# Sheet1_lora.net
KiCad netlist of a schematic drawn in Altium Designer
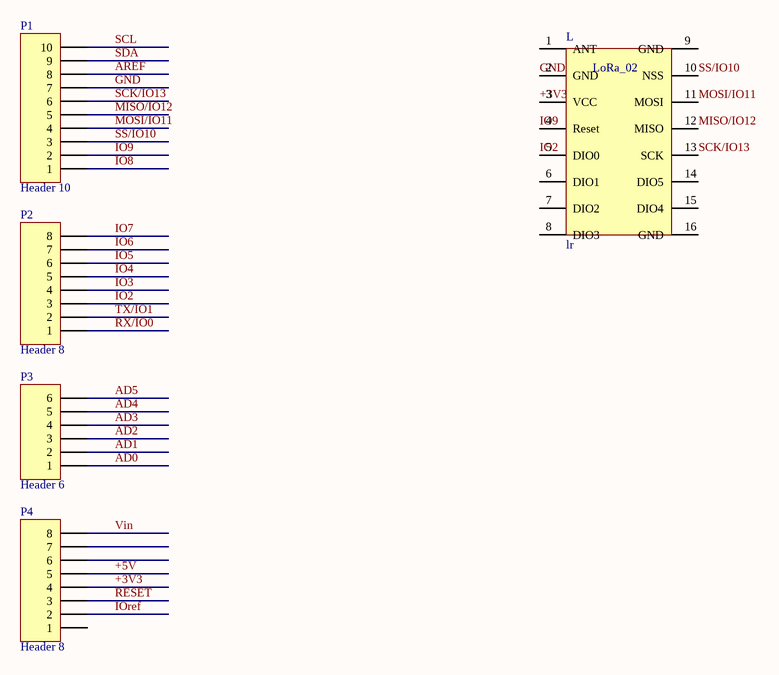
[diagram p0: Sheet1_lora.SchDoc]

(export (version "E")
  (design (tool "Eeschema 10.0.6"))
  (components
    (comp (ref "L") (value "lr") (footprint "LoRa") (libsource (lib "LoRa") (part "LoRa_Ra02")))
    (comp (ref "P1")
      (value "Header 10")
      (footprint "HDR1X10")
      (description "Header, 10-Pin")
      (fields (field (name "PUBLISHER") "Altium Limited"))
      (libsource (lib "Miscellaneous Connectors") (part "Header 10"))
    )
    (comp (ref "P2")
      (value "Header 8")
      (footprint "HDR1X8")
      (description "Header, 8-Pin")
      (fields (field (name "PUBLISHER") "Altium Limited"))
      (libsource (lib "Miscellaneous Connectors") (part "Header 8"))
    )
    (comp (ref "P3")
      (value "Header 6")
      (footprint "HDR1X6")
      (description "Header, 6-Pin")
      (fields (field (name "PUBLISHER") "Altium Limited"))
      (libsource (lib "Miscellaneous Connectors") (part "Header 6"))
    )
    (comp (ref "P4")
      (value "Header 8")
      (footprint "HDR1X8")
      (description "Header, 8-Pin")
      (fields (field (name "PUBLISHER") "Altium Limited"))
      (libsource (lib "Miscellaneous Connectors") (part "Header 8"))
    )
  )
  (nets
    (net (code "1") (name "/+3V3") (class "Default")
      (node (ref "L") (pin "3") (pinfunction "VCC_3") (pintype "passive"))
      (node (ref "P4") (pin "4") (pinfunction "4_4") (pintype "passive"))
    )
    (net (code "2") (name "/+5V") (class "Default")
      (node (ref "P4") (pin "5") (pinfunction "5_5") (pintype "passive"))
    )
    (net (code "3") (name "/AD0") (class "Default")
      (node (ref "P3") (pin "1") (pinfunction "1_1") (pintype "passive"))
    )
    (net (code "4") (name "/AD1") (class "Default")
      (node (ref "P3") (pin "2") (pinfunction "2_2") (pintype "passive"))
    )
    (net (code "5") (name "/AD2") (class "Default")
      (node (ref "P3") (pin "3") (pinfunction "3_3") (pintype "passive"))
    )
    (net (code "6") (name "/AD3") (class "Default")
      (node (ref "P3") (pin "4") (pinfunction "4_4") (pintype "passive"))
    )
    (net (code "7") (name "/AD4") (class "Default")
      (node (ref "P3") (pin "5") (pinfunction "5_5") (pintype "passive"))
    )
    (net (code "8") (name "/AD5") (class "Default")
      (node (ref "P3") (pin "6") (pinfunction "6_6") (pintype "passive"))
    )
    (net (code "9") (name "/AREF") (class "Default")
      (node (ref "P1") (pin "8") (pinfunction "8_8") (pintype "passive"))
    )
    (net (code "10") (name "/GND") (class "Default")
      (node (ref "L") (pin "2") (pinfunction "GND_2") (pintype "passive"))
      (node (ref "P1") (pin "7") (pinfunction "7_7") (pintype "passive"))
    )
    (net (code "11") (name "/IO2") (class "Default")
      (node (ref "L") (pin "5") (pinfunction "DIO0_5") (pintype "passive"))
      (node (ref "P2") (pin "3") (pinfunction "3_3") (pintype "passive"))
    )
    (net (code "12") (name "/IO3") (class "Default")
      (node (ref "P2") (pin "4") (pinfunction "4_4") (pintype "passive"))
    )
    (net (code "13") (name "/IO4") (class "Default")
      (node (ref "P2") (pin "5") (pinfunction "5_5") (pintype "passive"))
    )
    (net (code "14") (name "/IO5") (class "Default")
      (node (ref "P2") (pin "6") (pinfunction "6_6") (pintype "passive"))
    )
    (net (code "15") (name "/IO6") (class "Default")
      (node (ref "P2") (pin "7") (pinfunction "7_7") (pintype "passive"))
    )
    (net (code "16") (name "/IO7") (class "Default")
      (node (ref "P2") (pin "8") (pinfunction "8_8") (pintype "passive"))
    )
    (net (code "17") (name "/IO8") (class "Default")
      (node (ref "P1") (pin "1") (pinfunction "1_1") (pintype "passive"))
    )
    (net (code "18") (name "/IO9") (class "Default")
      (node (ref "L") (pin "4") (pinfunction "Reset_4") (pintype "passive"))
      (node (ref "P1") (pin "2") (pinfunction "2_2") (pintype "passive"))
    )
    (net (code "19") (name "/IOref") (class "Default")
      (node (ref "P4") (pin "2") (pinfunction "2_2") (pintype "passive"))
    )
    (net (code "20") (name "/MISO{slash}IO12") (class "Default")
      (node (ref "L") (pin "12") (pinfunction "MISO_12") (pintype "passive"))
      (node (ref "P1") (pin "5") (pinfunction "5_5") (pintype "passive"))
    )
    (net (code "21") (name "/MOSI{slash}IO11") (class "Default")
      (node (ref "L") (pin "11") (pinfunction "MOSI_11") (pintype "passive"))
      (node (ref "P1") (pin "4") (pinfunction "4_4") (pintype "passive"))
    )
    (net (code "22") (name "/RESET") (class "Default")
      (node (ref "P4") (pin "3") (pinfunction "3_3") (pintype "passive"))
    )
    (net (code "23") (name "/RX{slash}IO0") (class "Default")
      (node (ref "P2") (pin "1") (pinfunction "1_1") (pintype "passive"))
    )
    (net (code "24") (name "/SCK{slash}IO13") (class "Default")
      (node (ref "L") (pin "13") (pinfunction "SCK_13") (pintype "passive"))
      (node (ref "P1") (pin "6") (pinfunction "6_6") (pintype "passive"))
    )
    (net (code "25") (name "/SCL") (class "Default")
      (node (ref "P1") (pin "10") (pinfunction "10_10") (pintype "passive"))
    )
    (net (code "26") (name "/SDA") (class "Default")
      (node (ref "P1") (pin "9") (pinfunction "9_9") (pintype "passive"))
    )
    (net (code "27") (name "/SS{slash}IO10") (class "Default")
      (node (ref "L") (pin "10") (pinfunction "NSS_10") (pintype "passive"))
      (node (ref "P1") (pin "3") (pinfunction "3_3") (pintype "passive"))
    )
    (net (code "28") (name "/TX{slash}IO1") (class "Default")
      (node (ref "P2") (pin "2") (pinfunction "2_2") (pintype "passive"))
    )
    (net (code "29") (name "/Vin") (class "Default")
      (node (ref "P4") (pin "8") (pinfunction "8_8") (pintype "passive"))
    )
    (net (code "30") (name "unconnected-(L-ANT-Pad1)") (class "Default")
      (node (ref "L") (pin "1") (pinfunction "ANT_1") (pintype "passive"))
    )
    (net (code "31") (name "unconnected-(L-DIO1-Pad6)") (class "Default")
      (node (ref "L") (pin "6") (pinfunction "DIO1_6") (pintype "passive"))
    )
    (net (code "32") (name "unconnected-(L-DIO2-Pad7)") (class "Default")
      (node (ref "L") (pin "7") (pinfunction "DIO2_7") (pintype "passive"))
    )
    (net (code "33") (name "unconnected-(L-DIO3-Pad8)") (class "Default")
      (node (ref "L") (pin "8") (pinfunction "DIO3_8") (pintype "passive"))
    )
    (net (code "34") (name "unconnected-(L-DIO4-Pad15)") (class "Default")
      (node (ref "L") (pin "15") (pinfunction "DIO4_15") (pintype "passive"))
    )
    (net (code "35") (name "unconnected-(L-DIO5-Pad14)") (class "Default")
      (node (ref "L") (pin "14") (pinfunction "DIO5_14") (pintype "passive"))
    )
    (net (code "36") (name "unconnected-(L-GND-Pad9)") (class "Default")
      (node (ref "L") (pin "9") (pinfunction "GND_9") (pintype "passive"))
    )
    (net (code "37") (name "unconnected-(L-GND-Pad16)") (class "Default")
      (node (ref "L") (pin "16") (pinfunction "GND_16") (pintype "passive"))
    )
    (net (code "38") (name "unconnected-(P4-Pad1)") (class "Default")
      (node (ref "P4") (pin "1") (pinfunction "1_1") (pintype "passive"))
    )
    (net (code "39") (name "unconnected-(P4-Pad6)") (class "Default")
      (node (ref "P4") (pin "6") (pinfunction "6_6") (pintype "passive"))
    )
    (net (code "40") (name "unconnected-(P4-Pad7)") (class "Default")
      (node (ref "P4") (pin "7") (pinfunction "7_7") (pintype "passive"))
    )
  )
)
